# arduinoboardwithphotoresistors5-WillUpda.net
KiCad netlist of a schematic drawn in EAGLE
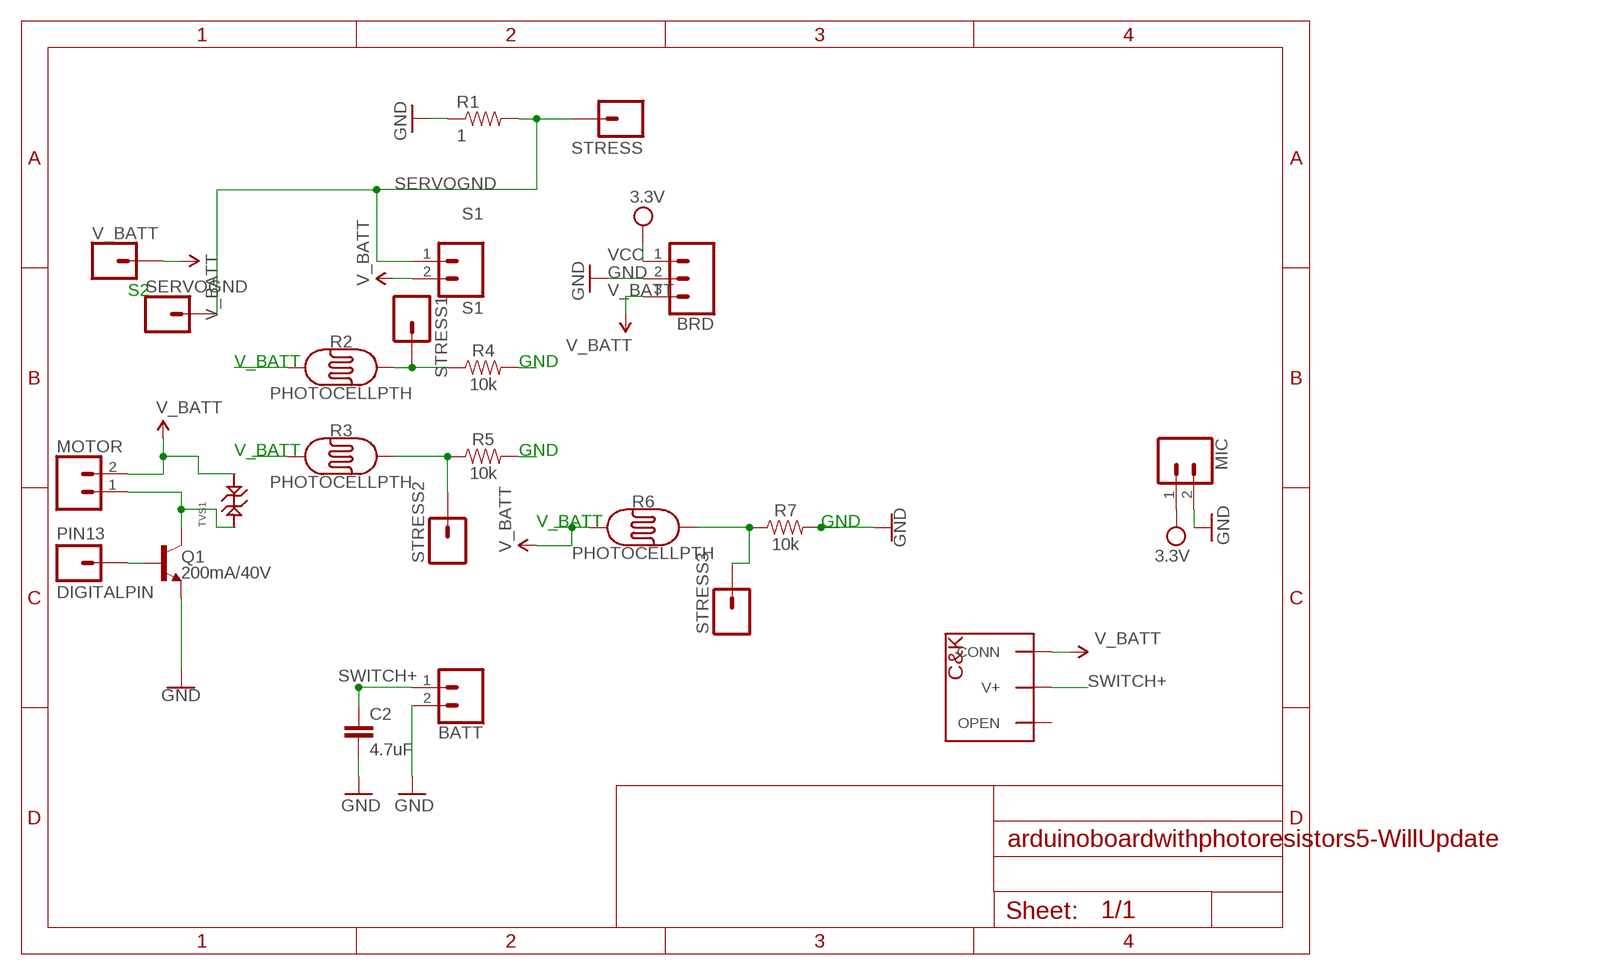
[diagram p0: schematic, sheet 1]

(export (version "E")
  (design (tool "Eeschema 10.0.6"))
  (components
    (comp (ref "BATT")
      (value "CONN_02")
      (footprint "eagle-import:1X02")
      (libsource (lib "eagle-import") (part "CONN_02"))
    )
    (comp (ref "BRD")
      (value "CONN_03")
      (footprint "eagle-import:1X03")
      (libsource (lib "eagle-import") (part "CONN_03"))
    )
    (comp (ref "C2")
      (value "4.7uF")
      (footprint "eagle-import:0603-CAP")
      (libsource (lib "eagle-import") (part "4.7UF-6.3V-10%(0603)0603"))
    )
    (comp (ref "MIC")
      (value "CONN_02")
      (footprint "eagle-import:1X02")
      (libsource (lib "eagle-import") (part "CONN_02"))
    )
    (comp (ref "MOTOR")
      (value "CONN_02")
      (footprint "eagle-import:1X02")
      (libsource (lib "eagle-import") (part "CONN_02"))
    )
    (comp (ref "PIN13")
      (value "DIGITALPIN")
      (footprint "eagle-import:1X01")
      (libsource (lib "eagle-import") (part "M01PTH"))
    )
    (comp (ref "Q1")
      (value "200mA/40V")
      (footprint "eagle-import:TO-92")
      (libsource (lib "eagle-import") (part "TRANS_NPN-2N3904"))
    )
    (comp (ref "R1")
      (value "1")
      (footprint "eagle-import:0603-RES")
      (libsource (lib "eagle-import") (part "2.0KOHM1/10W5%(0603)"))
    )
    (comp (ref "R2")
      (value "PHOTOCELLPTH")
      (footprint "eagle-import:PHOTOCELL")
      (libsource (lib "eagle-import") (part "PHOTOCELLPTH"))
    )
    (comp (ref "R3")
      (value "PHOTOCELLPTH")
      (footprint "eagle-import:PHOTOCELL")
      (libsource (lib "eagle-import") (part "PHOTOCELLPTH"))
    )
    (comp (ref "R4")
      (value "10k")
      (footprint "eagle-import:0603")
      (libsource (lib "eagle-import") (part "10KOHM-0603-1/10W-1%"))
    )
    (comp (ref "R5")
      (value "10k")
      (footprint "eagle-import:0603")
      (libsource (lib "eagle-import") (part "10KOHM-0603-1/10W-1%"))
    )
    (comp (ref "R6")
      (value "PHOTOCELLPTH")
      (footprint "eagle-import:PHOTOCELL")
      (libsource (lib "eagle-import") (part "PHOTOCELLPTH"))
    )
    (comp (ref "R7")
      (value "10k")
      (footprint "eagle-import:0603")
      (libsource (lib "eagle-import") (part "10KOHM-0603-1/10W-1%"))
    )
    (comp (ref "S1")
      (value "S1")
      (footprint "eagle-import:1X02")
      (libsource (lib "eagle-import") (part "CONN_02"))
    )
    (comp (ref "SERVOGND")
      (value "CONN_01")
      (footprint "eagle-import:1X01")
      (libsource (lib "eagle-import") (part "CONN_01"))
    )
    (comp (ref "STRESS")
      (value "M01PTH")
      (footprint "eagle-import:1X01")
      (libsource (lib "eagle-import") (part "M01PTH"))
    )
    (comp (ref "STRESS1")
      (value "M01PTH")
      (footprint "eagle-import:1X01")
      (libsource (lib "eagle-import") (part "M01PTH"))
    )
    (comp (ref "STRESS2")
      (value "M01PTH")
      (footprint "eagle-import:1X01")
      (libsource (lib "eagle-import") (part "M01PTH"))
    )
    (comp (ref "STRESS3")
      (value "M01PTH")
      (footprint "eagle-import:1X01")
      (libsource (lib "eagle-import") (part "M01PTH"))
    )
    (comp (ref "TVS1")
      (value "TVS_DIODE_SOD-923")
      (footprint "eagle-import:SOD-923")
      (libsource (lib "eagle-import") (part "TVS_DIODE_SOD-923"))
    )
    (comp (ref "U$1")
      (value "WILL-BLACKSLIDESWITCH")
      (footprint "eagle-import:WILL-BLACKSLIDESWITCH")
      (libsource (lib "eagle-import") (part "WILL-BLACKSLIDESWITCH"))
    )
    (comp (ref "V_BATT")
      (value "CONN_01")
      (footprint "eagle-import:1X01")
      (libsource (lib "eagle-import") (part "CONN_01"))
    )
  )
  (nets
    (net (code "1") (name "/SERVOGND") (class "Default")
      (node (ref "R1") (pin "2") (pinfunction "2_2") (pintype "passive"))
      (node (ref "S1") (pin "1") (pinfunction "1_1") (pintype "passive"))
      (node (ref "SERVOGND") (pin "1") (pinfunction "1_1") (pintype "passive"))
      (node (ref "STRESS") (pin "1") (pinfunction "1_1") (pintype "passive"))
    )
    (net (code "2") (name "/SWITCH+") (class "Default")
      (node (ref "BATT") (pin "1") (pinfunction "1_1") (pintype "passive"))
      (node (ref "C2") (pin "1") (pinfunction "1_1") (pintype "passive"))
      (node (ref "U$1") (pin "V+") (pinfunction "V+_V+") (pintype "bidirectional"))
    )
    (net (code "3") (name "3.3V") (class "Default")
      (node (ref "BRD") (pin "1") (pinfunction "1_1") (pintype "passive"))
      (node (ref "MIC") (pin "1") (pinfunction "1_1") (pintype "passive"))
    )
    (net (code "4") (name "GND") (class "Default")
      (node (ref "BATT") (pin "2") (pinfunction "2_2") (pintype "passive"))
      (node (ref "BRD") (pin "2") (pinfunction "2_2") (pintype "passive"))
      (node (ref "C2") (pin "2") (pinfunction "2_2") (pintype "passive"))
      (node (ref "MIC") (pin "2") (pinfunction "2_2") (pintype "passive"))
      (node (ref "Q1") (pin "1") (pinfunction "E_1") (pintype "passive"))
      (node (ref "R1") (pin "1") (pinfunction "1_1") (pintype "passive"))
      (node (ref "R4") (pin "2") (pinfunction "2_2") (pintype "passive"))
      (node (ref "R5") (pin "2") (pinfunction "2_2") (pintype "passive"))
      (node (ref "R7") (pin "2") (pinfunction "2_2") (pintype "passive"))
    )
    (net (code "5") (name "Net-(Q1-B)") (class "Default")
      (node (ref "PIN13") (pin "1") (pinfunction "1_1") (pintype "passive"))
      (node (ref "Q1") (pin "2") (pinfunction "B_2") (pintype "passive"))
    )
    (net (code "6") (name "Net-(Q1-C)") (class "Default")
      (node (ref "MOTOR") (pin "1") (pinfunction "1_1") (pintype "passive"))
      (node (ref "Q1") (pin "3") (pinfunction "C_3") (pintype "passive"))
      (node (ref "TVS1") (pin "P$1") (pinfunction "P$1_P$1") (pintype "bidirectional"))
    )
    (net (code "7") (name "Net-(R2-P$2)") (class "Default")
      (node (ref "R2") (pin "2") (pinfunction "P$2_2") (pintype "bidirectional"))
      (node (ref "R4") (pin "1") (pinfunction "1_1") (pintype "passive"))
      (node (ref "STRESS1") (pin "1") (pinfunction "1_1") (pintype "passive"))
    )
    (net (code "8") (name "Net-(R3-P$2)") (class "Default")
      (node (ref "R3") (pin "2") (pinfunction "P$2_2") (pintype "bidirectional"))
      (node (ref "R5") (pin "1") (pinfunction "1_1") (pintype "passive"))
      (node (ref "STRESS2") (pin "1") (pinfunction "1_1") (pintype "passive"))
    )
    (net (code "9") (name "Net-(R6-P$2)") (class "Default")
      (node (ref "R6") (pin "2") (pinfunction "P$2_2") (pintype "bidirectional"))
      (node (ref "R7") (pin "1") (pinfunction "1_1") (pintype "passive"))
      (node (ref "STRESS3") (pin "1") (pinfunction "1_1") (pintype "passive"))
    )
    (net (code "10") (name "V_BATT") (class "Default")
      (node (ref "BRD") (pin "3") (pinfunction "3_3") (pintype "passive"))
      (node (ref "MOTOR") (pin "2") (pinfunction "2_2") (pintype "passive"))
      (node (ref "R2") (pin "1") (pinfunction "P$1_1") (pintype "bidirectional"))
      (node (ref "R3") (pin "1") (pinfunction "P$1_1") (pintype "bidirectional"))
      (node (ref "R6") (pin "1") (pinfunction "P$1_1") (pintype "bidirectional"))
      (node (ref "S1") (pin "2") (pinfunction "2_2") (pintype "passive"))
      (node (ref "TVS1") (pin "P$2") (pinfunction "P$2_P$2") (pintype "bidirectional"))
      (node (ref "U$1") (pin "CONN") (pinfunction "CONN_CONN") (pintype "bidirectional"))
      (node (ref "V_BATT") (pin "1") (pinfunction "1_1") (pintype "passive"))
    )
    (net (code "11") (name "unconnected-(U$1-OPEN-PadNC)") (class "Default")
      (node (ref "U$1") (pin "NC") (pinfunction "OPEN_NC") (pintype "bidirectional"))
    )
  )
)
